# KNOB.net
KiCad netlist of a schematic drawn in Altium Designer
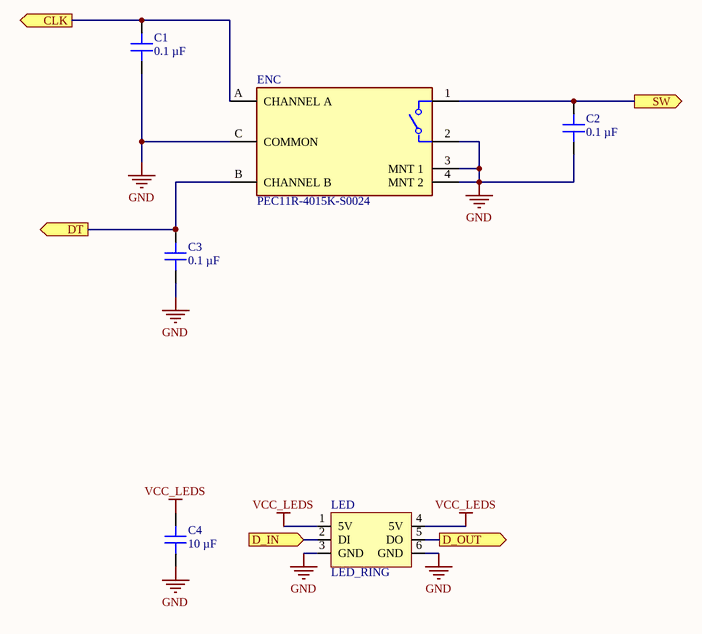
[diagram p0: KNOB.SchDoc]

(export (version "E")
  (design (tool "Eeschema 10.0.6"))
  (components
    (comp (ref "C1")
      (value "0.1 µF")
      (footprint "CAP 0603_1608")
      (description "CAP CER 0.1UF 16V X7R 0603")
      (fields (field (name "PART NUMBER") "CC0603KPX7R7BB104") (field (name "MANUFACTURER") "Yageo"))
      (libsource (lib "Celestial Altium Library - altium_library") (part "Capacitor"))
    )
    (comp (ref "C2")
      (value "0.1 µF")
      (footprint "CAP 0603_1608")
      (description "CAP CER 0.1UF 16V X7R 0603")
      (fields (field (name "PART NUMBER") "CC0603KPX7R7BB104") (field (name "MANUFACTURER") "Yageo"))
      (libsource (lib "Celestial Altium Library - altium_library") (part "Capacitor"))
    )
    (comp (ref "C3")
      (value "0.1 µF")
      (footprint "CAP 0603_1608")
      (description "CAP CER 0.1UF 16V X7R 0603")
      (fields (field (name "PART NUMBER") "CC0603KPX7R7BB104") (field (name "MANUFACTURER") "Yageo"))
      (libsource (lib "Celestial Altium Library - altium_library") (part "Capacitor"))
    )
    (comp (ref "C4")
      (value "10 µF")
      (footprint "MURATA GRM188 0603_1608")
      (description "CAP CER 10UF 10V X7R 0603")
      (fields
        (field (name "PART NUMBER") "GRM188Z71A106KA73D")
        (field (name "MANUFACTURER") "Murata Electronics")
      )
      (libsource (lib "Celestial Altium Library - altium_library") (part "Capacitor"))
    )
    (comp (ref "ENC")
      (value "PEC11R-4015K-S0024")
      (footprint "FP-PEC11R-4015K-S0024-MFG")
      (description "ROTARY ENCODER MECHANICAL 24PPR")
      (libsource (lib "Altium Content Vault") (part "61735aed983a166c614e16033f3d545"))
    )
    (comp (ref "LED")
      (value "LED_RING")
      (footprint "KNOOBS:LED_RING")
      (libsource (lib "KNOOBS") (part "LED_RING"))
    )
  )
  (nets
    (net (code "1") (name "/CLK") (class "Default")
      (node (ref "C1") (pin "2") (pinfunction "2_2") (pintype "passive"))
      (node (ref "ENC") (pin "A") (pinfunction "CHANNEL_A_A") (pintype "passive"))
    )
    (net (code "2") (name "/DT") (class "Default")
      (node (ref "C3") (pin "2") (pinfunction "2_2") (pintype "passive"))
      (node (ref "ENC") (pin "B") (pinfunction "CHANNEL_B_B") (pintype "passive"))
    )
    (net (code "3") (name "/D_IN") (class "Default")
      (node (ref "LED") (pin "2") (pinfunction "DI_2") (pintype "passive"))
    )
    (net (code "4") (name "/D_OUT") (class "Default")
      (node (ref "LED") (pin "5") (pinfunction "DO_5") (pintype "passive"))
    )
    (net (code "5") (name "/SW") (class "Default")
      (node (ref "C2") (pin "2") (pinfunction "2_2") (pintype "passive"))
      (node (ref "ENC") (pin "1") (pinfunction "1_1") (pintype "passive"))
    )
    (net (code "6") (name "GND") (class "Default")
      (node (ref "C1") (pin "1") (pinfunction "1_1") (pintype "passive"))
      (node (ref "C2") (pin "1") (pinfunction "1_1") (pintype "passive"))
      (node (ref "C3") (pin "1") (pinfunction "1_1") (pintype "passive"))
      (node (ref "C4") (pin "1") (pinfunction "1_1") (pintype "passive"))
      (node (ref "ENC") (pin "2") (pinfunction "2_2") (pintype "passive"))
      (node (ref "ENC") (pin "3") (pinfunction "MNT_1_3") (pintype "passive"))
      (node (ref "ENC") (pin "4") (pinfunction "MNT_2_4") (pintype "passive"))
      (node (ref "ENC") (pin "C") (pinfunction "COMMON_C") (pintype "passive"))
      (node (ref "LED") (pin "3") (pinfunction "GND_3") (pintype "passive"))
      (node (ref "LED") (pin "6") (pinfunction "GND_6") (pintype "passive"))
    )
    (net (code "7") (name "VCC_LEDS") (class "Default")
      (node (ref "C4") (pin "2") (pinfunction "2_2") (pintype "passive"))
      (node (ref "LED") (pin "1") (pinfunction "5V_1") (pintype "passive"))
      (node (ref "LED") (pin "4") (pinfunction "5V_4") (pintype "passive"))
    )
  )
)
